# mach_sac.net
KiCad netlist of a schematic drawn in Altium Designer
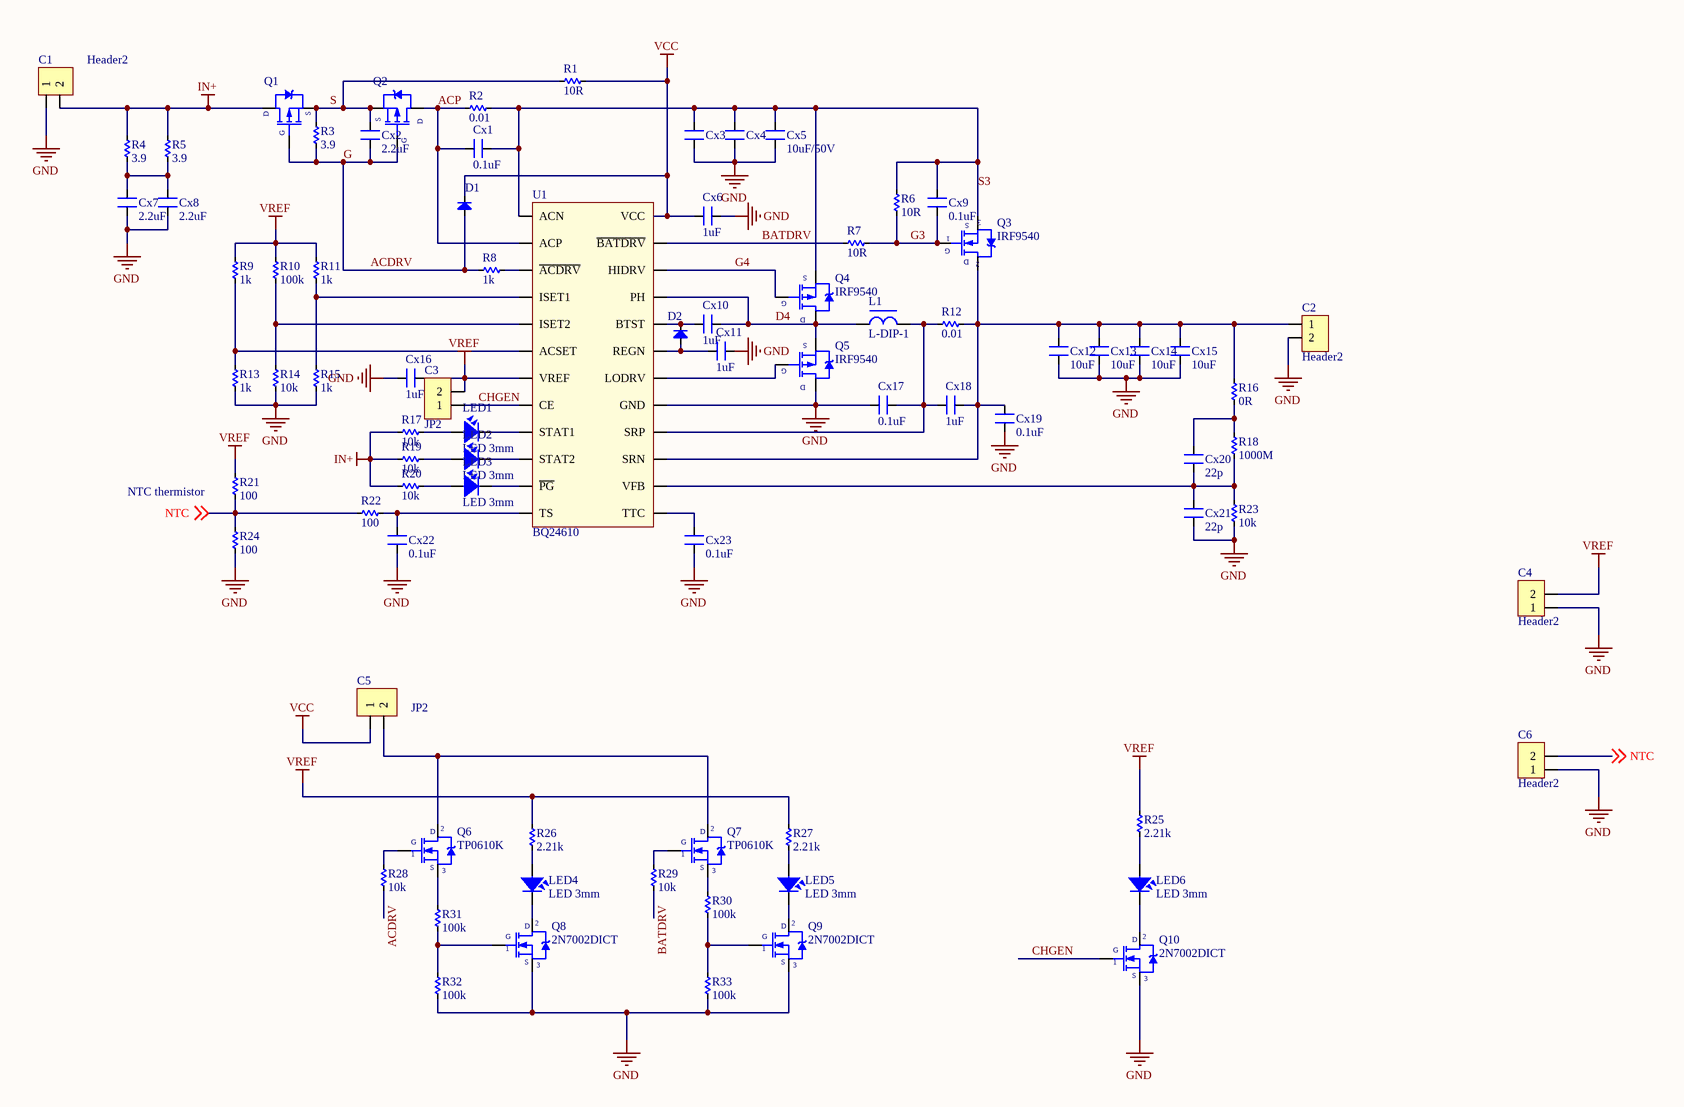
[diagram p0: mach sac.SchDoc]

(export (version "E")
  (design (tool "Eeschema 10.0.6"))
  (components
    (comp (ref "C1")
      (value "Header2")
      (footprint "HDR2")
      (description "Header IDC, 2 x 1 Pin Vertical 2.54mm Pitch (Non-Boxed, Male)")
      (fields
        (field (name "MANUFACTURER") "Würth Elektronik eiSos GmbH")
        (field (name "PARTNO") "613002143121")
        (field (name "CREATED BY") "Karrer Zheng")
      )
      (libsource (lib "") (part "Header2_1"))
    )
    (comp (ref "C2")
      (value "Header2")
      (footprint "HDR2")
      (description "Header IDC, 2 x 1 Pin Vertical 2.54mm Pitch (Non-Boxed, Male)")
      (fields
        (field (name "MANUFACTURER") "Würth Elektronik eiSos GmbH")
        (field (name "PARTNO") "613002143121")
        (field (name "CREATED BY") "Karrer Zheng")
      )
      (libsource (lib "") (part "Header2_2"))
    )
    (comp (ref "C3")
      (value "JP2")
      (footprint "JP2-CLOSED")
      (description "WR-PHD 2.54 mm Angled Socket Header")
      (fields
        (field (name "MANUFACTURER") "Würth Elektronik eiSos GmbH")
        (field (name "PARTNO") "613002143121")
        (field (name "CREATED BY") "Karrer Zheng")
      )
      (libsource (lib "") (part "JP2_1"))
    )
    (comp (ref "C4")
      (value "Header2")
      (footprint "HDR2")
      (description "Header IDC, 2 x 1 Pin Vertical 2.54mm Pitch (Non-Boxed, Male)")
      (fields
        (field (name "MANUFACTURER") "Würth Elektronik eiSos GmbH")
        (field (name "PARTNO") "613002143121")
        (field (name "CREATED BY") "Karrer Zheng")
      )
      (libsource (lib "LIBRARY") (part "Header2"))
    )
    (comp (ref "C5")
      (value "JP2")
      (footprint "JP2-C1T")
      (description "WR-PHD 2.54 mm Angled Socket Header")
      (fields
        (field (name "MANUFACTURER") "Würth Elektronik eiSos GmbH")
        (field (name "PARTNO") "613002143121")
        (field (name "CREATED BY") "Karrer Zheng")
      )
      (libsource (lib "ImetAltiumLibrary") (part "JP2"))
    )
    (comp (ref "C6")
      (value "Header2")
      (footprint "HDR2")
      (description "Header IDC, 2 x 1 Pin Vertical 2.54mm Pitch (Non-Boxed, Male)")
      (fields
        (field (name "MANUFACTURER") "Würth Elektronik eiSos GmbH")
        (field (name "PARTNO") "613002143121")
        (field (name "CREATED BY") "Karrer Zheng")
      )
      (libsource (lib "LIBRARY") (part "Header2"))
    )
    (comp (ref "Cx1") (value "0.1uF") (footprint "C0805") (libsource (lib "LIBRARY") (part "CN")))
    (comp (ref "Cx2") (value "2.2uF") (footprint "C0805") (libsource (lib "LIBRARY") (part "CN")))
    (comp (ref "Cx3") (value "10uF/50V") (footprint "C0805") (libsource (lib "LIBRARY") (part "CN")))
    (comp (ref "Cx4") (value "10uF/50V") (footprint "C0805") (libsource (lib "LIBRARY") (part "CN")))
    (comp (ref "Cx5") (value "10uF/50V") (footprint "C0805") (libsource (lib "LIBRARY") (part "CN")))
    (comp (ref "Cx6") (value "1uF") (footprint "C0805") (libsource (lib "LIBRARY") (part "CN")))
    (comp (ref "Cx7") (value "2.2uF") (footprint "C0805") (libsource (lib "LIBRARY") (part "CN")))
    (comp (ref "Cx8") (value "2.2uF") (footprint "C0805") (libsource (lib "LIBRARY") (part "CN")))
    (comp (ref "Cx9") (value "0.1uF") (footprint "C0805") (libsource (lib "LIBRARY") (part "CN")))
    (comp (ref "Cx10") (value "1uF") (footprint "C0805") (libsource (lib "LIBRARY") (part "CN")))
    (comp (ref "Cx11") (value "1uF") (footprint "C0805") (libsource (lib "LIBRARY") (part "CN")))
    (comp (ref "Cx12") (value "10uF") (footprint "C0805") (libsource (lib "LIBRARY") (part "CN")))
    (comp (ref "Cx13") (value "10uF") (footprint "C0805") (libsource (lib "LIBRARY") (part "CN")))
    (comp (ref "Cx14") (value "10uF") (footprint "C0805") (libsource (lib "LIBRARY") (part "CN")))
    (comp (ref "Cx15") (value "10uF") (footprint "C0805") (libsource (lib "LIBRARY") (part "CN")))
    (comp (ref "Cx16") (value "1uF") (footprint "C0805") (libsource (lib "LIBRARY") (part "CN")))
    (comp (ref "Cx17") (value "0.1uF") (footprint "C0805") (libsource (lib "LIBRARY") (part "CN")))
    (comp (ref "Cx18") (value "1uF") (footprint "C0805") (libsource (lib "LIBRARY") (part "CN")))
    (comp (ref "Cx19") (value "0.1uF") (footprint "C0805") (libsource (lib "LIBRARY") (part "CN")))
    (comp (ref "Cx20") (value "22p") (footprint "C0805") (libsource (lib "LIBRARY") (part "CN")))
    (comp (ref "Cx21") (value "22p") (footprint "C0805") (libsource (lib "LIBRARY") (part "CN")))
    (comp (ref "Cx22") (value "0.1uF") (footprint "C0805") (libsource (lib "LIBRARY") (part "CN")))
    (comp (ref "Cx23") (value "0.1uF") (footprint "C0805") (libsource (lib "LIBRARY") (part "CN")))
    (comp (ref "D1")
      (value "Diode")
      (footprint "DIO-1A")
      (description "Default Diode")
      (fields (field (name "PUBLISHER") "Altium Limited"))
      (libsource (lib "ImetAltiumLibrary") (part "Diode"))
    )
    (comp (ref "D2")
      (value "Diode")
      (footprint "DIO-1A")
      (description "Default Diode")
      (fields (field (name "PUBLISHER") "Altium Limited"))
      (libsource (lib "ImetAltiumLibrary") (part "Diode"))
    )
    (comp (ref "L1")
      (value "L-DIP-1")
      (footprint "L-SMD-D-12.5x12.5")
      (description "Inductor")
      (libsource (lib "ImetAltiumLibrary") (part "L-DIP-1"))
    )
    (comp (ref "LED1")
      (value "LED 3mm")
      (footprint "Led SMD")
      (description "LED Single colour Green and Red")
      (libsource (lib "PELAB") (part "LED 3mm"))
    )
    (comp (ref "LED2")
      (value "LED 3mm")
      (footprint "Led SMD")
      (description "LED Single colour Green and Red")
      (libsource (lib "PELAB") (part "LED 3mm"))
    )
    (comp (ref "LED3")
      (value "LED 3mm")
      (footprint "Led SMD")
      (description "LED Single colour Green and Red")
      (libsource (lib "PELAB") (part "LED 3mm"))
    )
    (comp (ref "LED4")
      (value "LED 3mm")
      (footprint "Led SMD")
      (description "LED Single colour Green and Red")
      (libsource (lib "PELAB") (part "LED 3mm"))
    )
    (comp (ref "LED5")
      (value "LED 3mm")
      (footprint "Led SMD")
      (description "LED Single colour Green and Red")
      (libsource (lib "PELAB") (part "LED 3mm"))
    )
    (comp (ref "LED6")
      (value "LED 3mm")
      (footprint "Led SMD")
      (description "LED Single colour Green and Red")
      (libsource (lib "PELAB") (part "LED 3mm"))
    )
    (comp (ref "Q1")
      (value "IRF9540")
      (footprint "SO-8")
      (description "HEXFET P-Channel Power MOSFET")
      (fields (field (name "PUBLISHER") "Altium Limited"))
      (libsource (lib "PELAB") (part "IRF9540"))
    )
    (comp (ref "Q2")
      (value "IRF9540")
      (footprint "SO-8")
      (description "HEXFET P-Channel Power MOSFET")
      (fields (field (name "PUBLISHER") "Altium Limited"))
      (libsource (lib "ImetAltiumLibrary") (part "IRF9540"))
    )
    (comp (ref "Q3")
      (value "IRF9540")
      (footprint "SO-8")
      (description "MOSFET N - CHANNEL 500V - 0.75 - 8A - TO-220")
      (libsource (lib "ImetAltiumLibrary") (part "IRF840"))
    )
    (comp (ref "Q4")
      (value "IRF9540")
      (footprint "SO-8")
      (description "HEXFET P-Channel Power MOSFET")
      (libsource (lib "LIBRARY") (part "IRF9540"))
    )
    (comp (ref "Q5")
      (value "IRF9540")
      (footprint "SO-8")
      (description "HEXFET P-Channel Power MOSFET")
      (libsource (lib "LIBRARY") (part "IRF9540"))
    )
    (comp (ref "Q6")
      (value "TP0610K")
      (footprint "SOT23-132")
      (description "MOSFET N - CHANNEL 500V - 0.75 - 8A - TO-220")
      (libsource (lib "ImetAltiumLibrary") (part "IRF840"))
    )
    (comp (ref "Q7")
      (value "TP0610K")
      (footprint "SOT23-132")
      (description "MOSFET N - CHANNEL 500V - 0.75 - 8A - TO-220")
      (libsource (lib "ImetAltiumLibrary") (part "IRF840"))
    )
    (comp (ref "Q8")
      (value "2N7002DICT")
      (footprint "SOT23-132")
      (description "MOSFET N - CHANNEL 500V - 0.75 - 8A - TO-220")
      (libsource (lib "ImetAltiumLibrary") (part "IRF840"))
    )
    (comp (ref "Q9")
      (value "2N7002DICT")
      (footprint "SOT23-132")
      (description "MOSFET N - CHANNEL 500V - 0.75 - 8A - TO-220")
      (libsource (lib "ImetAltiumLibrary") (part "IRF840"))
    )
    (comp (ref "Q10")
      (value "2N7002DICT")
      (footprint "SOT23-132")
      (description "MOSFET N - CHANNEL 500V - 0.75 - 8A - TO-220")
      (libsource (lib "ImetAltiumLibrary") (part "IRF840"))
    )
    (comp (ref "R1")
      (value "10R")
      (footprint "Resistor:RES-SMD-0805")
      (description "Resistor")
      (fields
        (field (name "MANUFACTURER") "Generic Components")
        (field (name "PUBLISHER") "Altium Hobart Technology Centre")
      )
      (libsource (lib "LIBRARY") (part "Res-SMD"))
    )
    (comp (ref "R2")
      (value "0.01")
      (footprint "RES-SMD-1210")
      (description "Resistor")
      (fields
        (field (name "MANUFACTURER") "Generic Components")
        (field (name "PUBLISHER") "Altium Hobart Technology Centre")
      )
      (libsource (lib "LIBRARY") (part "Res-SMD"))
    )
    (comp (ref "R3")
      (value "3.9")
      (footprint "Resistor:RES-SMD-0805")
      (description "Resistor")
      (fields
        (field (name "MANUFACTURER") "Generic Components")
        (field (name "PUBLISHER") "Altium Hobart Technology Centre")
      )
      (libsource (lib "LIBRARY") (part "Res-SMD"))
    )
    (comp (ref "R4")
      (value "3.9")
      (footprint "Resistor:RES-SMD-0805")
      (description "Resistor")
      (fields
        (field (name "MANUFACTURER") "Generic Components")
        (field (name "PUBLISHER") "Altium Hobart Technology Centre")
      )
      (libsource (lib "LIBRARY") (part "Res-SMD"))
    )
    (comp (ref "R5")
      (value "3.9")
      (footprint "Resistor:RES-SMD-0805")
      (description "Resistor")
      (fields
        (field (name "MANUFACTURER") "Generic Components")
        (field (name "PUBLISHER") "Altium Hobart Technology Centre")
      )
      (libsource (lib "LIBRARY") (part "Res-SMD"))
    )
    (comp (ref "R6")
      (value "10R")
      (footprint "Resistor:RES-SMD-0805")
      (description "Resistor")
      (fields
        (field (name "MANUFACTURER") "Generic Components")
        (field (name "PUBLISHER") "Altium Hobart Technology Centre")
      )
      (libsource (lib "LIBRARY") (part "Res-SMD"))
    )
    (comp (ref "R7")
      (value "10R")
      (footprint "Resistor:RES-SMD-0805")
      (description "Resistor")
      (fields
        (field (name "MANUFACTURER") "Generic Components")
        (field (name "PUBLISHER") "Altium Hobart Technology Centre")
      )
      (libsource (lib "LIBRARY") (part "Res-SMD"))
    )
    (comp (ref "R8")
      (value "1k")
      (footprint "Resistor:RES-SMD-0805")
      (description "Resistor")
      (fields
        (field (name "MANUFACTURER") "Generic Components")
        (field (name "PUBLISHER") "Altium Hobart Technology Centre")
      )
      (libsource (lib "LIBRARY") (part "Res-SMD"))
    )
    (comp (ref "R9")
      (value "1k")
      (footprint "Resistor:RES-SMD-0805")
      (description "Resistor")
      (fields
        (field (name "MANUFACTURER") "Generic Components")
        (field (name "PUBLISHER") "Altium Hobart Technology Centre")
      )
      (libsource (lib "LIBRARY") (part "Res-SMD"))
    )
    (comp (ref "R10")
      (value "100k")
      (footprint "Resistor:RES-SMD-0805")
      (description "Resistor")
      (fields
        (field (name "MANUFACTURER") "Generic Components")
        (field (name "PUBLISHER") "Altium Hobart Technology Centre")
      )
      (libsource (lib "LIBRARY") (part "Res-SMD"))
    )
    (comp (ref "R11")
      (value "1k")
      (footprint "Resistor:RES-SMD-0805")
      (description "Resistor")
      (fields
        (field (name "MANUFACTURER") "Generic Components")
        (field (name "PUBLISHER") "Altium Hobart Technology Centre")
      )
      (libsource (lib "LIBRARY") (part "Res-SMD"))
    )
    (comp (ref "R12")
      (value "0.01")
      (footprint "RES-SMD-1210")
      (description "Resistor")
      (fields
        (field (name "MANUFACTURER") "Generic Components")
        (field (name "PUBLISHER") "Altium Hobart Technology Centre")
      )
      (libsource (lib "ImetAltiumLibrary") (part "Res-SMD"))
    )
    (comp (ref "R13")
      (value "1k")
      (footprint "Resistor:RES-SMD-0805")
      (description "Resistor")
      (fields
        (field (name "MANUFACTURER") "Generic Components")
        (field (name "PUBLISHER") "Altium Hobart Technology Centre")
      )
      (libsource (lib "LIBRARY") (part "Res-SMD"))
    )
    (comp (ref "R14")
      (value "10k")
      (footprint "Resistor:RES-SMD-0805")
      (description "Resistor")
      (fields
        (field (name "MANUFACTURER") "Generic Components")
        (field (name "PUBLISHER") "Altium Hobart Technology Centre")
      )
      (libsource (lib "LIBRARY") (part "Res-SMD"))
    )
    (comp (ref "R15")
      (value "1k")
      (footprint "Resistor:RES-SMD-0805")
      (description "Resistor")
      (fields
        (field (name "MANUFACTURER") "Generic Components")
        (field (name "PUBLISHER") "Altium Hobart Technology Centre")
      )
      (libsource (lib "LIBRARY") (part "Res-SMD"))
    )
    (comp (ref "R16")
      (value "0R")
      (footprint "Resistor:RES-SMD-0805")
      (description "Resistor")
      (fields
        (field (name "MANUFACTURER") "Generic Components")
        (field (name "PUBLISHER") "Altium Hobart Technology Centre")
      )
      (libsource (lib "LIBRARY") (part "Res-SMD"))
    )
    (comp (ref "R17")
      (value "10k")
      (footprint "Resistor:RES-SMD-0805")
      (description "Resistor")
      (fields
        (field (name "MANUFACTURER") "Generic Components")
        (field (name "PUBLISHER") "Altium Hobart Technology Centre")
      )
      (libsource (lib "LIBRARY") (part "Res-SMD"))
    )
    (comp (ref "R18")
      (value "1000M")
      (footprint "Resistor:RES-SMD-0805")
      (description "Resistor")
      (fields
        (field (name "MANUFACTURER") "Generic Components")
        (field (name "PUBLISHER") "Altium Hobart Technology Centre")
      )
      (libsource (lib "LIBRARY") (part "Res-SMD"))
    )
    (comp (ref "R19")
      (value "10k")
      (footprint "Resistor:RES-SMD-0805")
      (description "Resistor")
      (fields
        (field (name "MANUFACTURER") "Generic Components")
        (field (name "PUBLISHER") "Altium Hobart Technology Centre")
      )
      (libsource (lib "LIBRARY") (part "Res-SMD"))
    )
    (comp (ref "R20")
      (value "10k")
      (footprint "Resistor:RES-SMD-0805")
      (description "Resistor")
      (fields
        (field (name "MANUFACTURER") "Generic Components")
        (field (name "PUBLISHER") "Altium Hobart Technology Centre")
      )
      (libsource (lib "LIBRARY") (part "Res-SMD"))
    )
    (comp (ref "R21")
      (value "100")
      (footprint "Resistor:RES-SMD-0805")
      (description "Resistor")
      (fields
        (field (name "MANUFACTURER") "Generic Components")
        (field (name "PUBLISHER") "Altium Hobart Technology Centre")
      )
      (libsource (lib "LIBRARY") (part "Res-SMD"))
    )
    (comp (ref "R22")
      (value "100")
      (footprint "Resistor:RES-SMD-0805")
      (description "Resistor")
      (fields
        (field (name "MANUFACTURER") "Generic Components")
        (field (name "PUBLISHER") "Altium Hobart Technology Centre")
      )
      (libsource (lib "LIBRARY") (part "Res-SMD"))
    )
    (comp (ref "R23")
      (value "10k")
      (footprint "Resistor:RES-SMD-0805")
      (description "Resistor")
      (fields
        (field (name "MANUFACTURER") "Generic Components")
        (field (name "PUBLISHER") "Altium Hobart Technology Centre")
      )
      (libsource (lib "ImetAltiumLibrary") (part "Res-SMD"))
    )
    (comp (ref "R24")
      (value "100")
      (footprint "Resistor:RES-SMD-0805")
      (description "Resistor")
      (fields
        (field (name "MANUFACTURER") "Generic Components")
        (field (name "PUBLISHER") "Altium Hobart Technology Centre")
      )
      (libsource (lib "LIBRARY") (part "Res-SMD"))
    )
    (comp (ref "R25")
      (value "2.21k")
      (footprint "RES-SMD-0603")
      (description "Resistor")
      (fields
        (field (name "MANUFACTURER") "Generic Components")
        (field (name "PUBLISHER") "Altium Hobart Technology Centre")
      )
      (libsource (lib "ImetAltiumLibrary") (part "Res-SMD"))
    )
    (comp (ref "R26")
      (value "2.21k")
      (footprint "RES-SMD-0603")
      (description "Resistor")
      (fields
        (field (name "MANUFACTURER") "Generic Components")
        (field (name "PUBLISHER") "Altium Hobart Technology Centre")
      )
      (libsource (lib "ImetAltiumLibrary") (part "Res-SMD"))
    )
    (comp (ref "R27")
      (value "2.21k")
      (footprint "RES-SMD-0603")
      (description "Resistor")
      (fields
        (field (name "MANUFACTURER") "Generic Components")
        (field (name "PUBLISHER") "Altium Hobart Technology Centre")
      )
      (libsource (lib "ImetAltiumLibrary") (part "Res-SMD"))
    )
    (comp (ref "R28")
      (value "10k")
      (footprint "RES-SMD-0603")
      (description "Resistor")
      (fields
        (field (name "MANUFACTURER") "Generic Components")
        (field (name "PUBLISHER") "Altium Hobart Technology Centre")
      )
      (libsource (lib "ImetAltiumLibrary") (part "Res-SMD"))
    )
    (comp (ref "R29")
      (value "10k")
      (footprint "RES-SMD-0603")
      (description "Resistor")
      (fields
        (field (name "MANUFACTURER") "Generic Components")
        (field (name "PUBLISHER") "Altium Hobart Technology Centre")
      )
      (libsource (lib "ImetAltiumLibrary") (part "Res-SMD"))
    )
    (comp (ref "R30")
      (value "100k")
      (footprint "RES-SMD-0603")
      (description "Resistor")
      (fields
        (field (name "MANUFACTURER") "Generic Components")
        (field (name "PUBLISHER") "Altium Hobart Technology Centre")
      )
      (libsource (lib "ImetAltiumLibrary") (part "Res-SMD"))
    )
    (comp (ref "R31")
      (value "100k")
      (footprint "RES-SMD-0603")
      (description "Resistor")
      (fields
        (field (name "MANUFACTURER") "Generic Components")
        (field (name "PUBLISHER") "Altium Hobart Technology Centre")
      )
      (libsource (lib "ImetAltiumLibrary") (part "Res-SMD"))
    )
    (comp (ref "R32")
      (value "100k")
      (footprint "RES-SMD-0603")
      (description "Resistor")
      (fields
        (field (name "MANUFACTURER") "Generic Components")
        (field (name "PUBLISHER") "Altium Hobart Technology Centre")
      )
      (libsource (lib "ImetAltiumLibrary") (part "Res-SMD"))
    )
    (comp (ref "R33")
      (value "100k")
      (footprint "RES-SMD-0603")
      (description "Resistor")
      (fields
        (field (name "MANUFACTURER") "Generic Components")
        (field (name "PUBLISHER") "Altium Hobart Technology Centre")
      )
      (libsource (lib "ImetAltiumLibrary") (part "Res-SMD"))
    )
    (comp (ref "U1")
      (value "BQ24610")
      (footprint "QFN50P400X400X100_HS-25N")
      (description "DIP24")
      (libsource (lib "PELAB") (part "BQ24610"))
    )
  )
  (nets
    (net (code "1") (name "/ACDRV") (class "Default")
      (node (ref "Cx2") (pin "1") (pinfunction "1_1") (pintype "passive"))
      (node (ref "D1") (pin "1") (pinfunction "A_1") (pintype "passive"))
      (node (ref "Q1") (pin "1") (pinfunction "G_1") (pintype "passive"))
      (node (ref "Q2") (pin "1") (pinfunction "G_1") (pintype "passive"))
      (node (ref "R28") (pin "2") (pinfunction "2_2") (pintype "passive"))
      (node (ref "R3") (pin "2") (pinfunction "2_2") (pintype "passive"))
      (node (ref "R8") (pin "1") (pinfunction "1_1") (pintype "passive"))
    )
    (net (code "2") (name "/ACP") (class "Default")
      (node (ref "Cx1") (pin "2") (pinfunction "2_2") (pintype "passive"))
      (node (ref "Q2") (pin "2") (pinfunction "D_2") (pintype "passive"))
      (node (ref "R2") (pin "2") (pinfunction "2_2") (pintype "passive"))
      (node (ref "U1") (pin "2") (pinfunction "ACP_2") (pintype "passive"))
    )
    (net (code "3") (name "/BATDRV") (class "Default")
      (node (ref "R29") (pin "2") (pinfunction "2_2") (pintype "passive"))
      (node (ref "R7") (pin "1") (pinfunction "1_1") (pintype "passive"))
      (node (ref "U1") (pin "23") (pinfunction "~{BATDRV}_23") (pintype "passive"))
    )
    (net (code "4") (name "/CHGEN") (class "Default")
      (node (ref "C3") (pin "1") (pinfunction "1_1") (pintype "passive"))
      (node (ref "Q10") (pin "1") (pinfunction "G_1") (pintype "passive"))
      (node (ref "U1") (pin "4") (pinfunction "CE_4") (pintype "passive"))
    )
    (net (code "5") (name "/D4") (class "Default")
      (node (ref "Cx10") (pin "1") (pinfunction "1_1") (pintype "passive"))
      (node (ref "L1") (pin "1") (pinfunction "1_1") (pintype "passive"))
      (node (ref "Q4") (pin "2") (pinfunction "D_2") (pintype "passive"))
      (node (ref "Q5") (pin "3") (pinfunction "S_3") (pintype "passive"))
      (node (ref "U1") (pin "20") (pinfunction "PH_20") (pintype "passive"))
    )
    (net (code "6") (name "/G3") (class "Default")
      (node (ref "Cx9") (pin "2") (pinfunction "2_2") (pintype "passive"))
      (node (ref "Q3") (pin "1") (pinfunction "G_1") (pintype "passive"))
      (node (ref "R6") (pin "1") (pinfunction "1_1") (pintype "passive"))
      (node (ref "R7") (pin "2") (pinfunction "2_2") (pintype "passive"))
    )
    (net (code "7") (name "/G4") (class "Default")
      (node (ref "Q4") (pin "1") (pinfunction "G_1") (pintype "passive"))
      (node (ref "U1") (pin "21") (pinfunction "HIDRV_21") (pintype "passive"))
    )
    (net (code "8") (name "/S") (class "Default")
      (node (ref "Cx2") (pin "2") (pinfunction "2_2") (pintype "passive"))
      (node (ref "Q1") (pin "3") (pinfunction "S_3") (pintype "passive"))
      (node (ref "Q2") (pin "3") (pinfunction "S_3") (pintype "passive"))
      (node (ref "R1") (pin "1") (pinfunction "1_1") (pintype "passive"))
      (node (ref "R3") (pin "1") (pinfunction "1_1") (pintype "passive"))
    )
    (net (code "9") (name "/S3") (class "Default")
      (node (ref "Cx1") (pin "1") (pinfunction "1_1") (pintype "passive"))
      (node (ref "Cx3") (pin "1") (pinfunction "1_1") (pintype "passive"))
      (node (ref "Cx4") (pin "1") (pinfunction "1_1") (pintype "passive"))
      (node (ref "Cx5") (pin "1") (pinfunction "1_1") (pintype "passive"))
      (node (ref "Cx9") (pin "1") (pinfunction "1_1") (pintype "passive"))
      (node (ref "Q3") (pin "3") (pinfunction "S_3") (pintype "passive"))
      (node (ref "Q4") (pin "3") (pinfunction "S_3") (pintype "passive"))
      (node (ref "R2") (pin "1") (pinfunction "1_1") (pintype "passive"))
      (node (ref "R6") (pin "2") (pinfunction "2_2") (pintype "passive"))
      (node (ref "U1") (pin "1") (pinfunction "ACN_1") (pintype "passive"))
    )
    (net (code "10") (name "GND") (class "Default")
      (node (ref "C1") (pin "1") (pinfunction "1_1") (pintype "passive"))
      (node (ref "C2") (pin "2") (pinfunction "2_2") (pintype "passive"))
      (node (ref "C4") (pin "1") (pinfunction "1_1") (pintype "passive"))
      (node (ref "C6") (pin "1") (pinfunction "1_1") (pintype "passive"))
      (node (ref "Cx11") (pin "1") (pinfunction "1_1") (pintype "passive"))
      (node (ref "Cx12") (pin "2") (pinfunction "2_2") (pintype "passive"))
      (node (ref "Cx13") (pin "2") (pinfunction "2_2") (pintype "passive"))
      (node (ref "Cx14") (pin "2") (pinfunction "2_2") (pintype "passive"))
      (node (ref "Cx15") (pin "2") (pinfunction "2_2") (pintype "passive"))
      (node (ref "Cx16") (pin "1") (pinfunction "1_1") (pintype "passive"))
      (node (ref "Cx17") (pin "2") (pinfunction "2_2") (pintype "passive"))
      (node (ref "Cx19") (pin "2") (pinfunction "2_2") (pintype "passive"))
      (node (ref "Cx21") (pin "2") (pinfunction "2_2") (pintype "passive"))
      (node (ref "Cx22") (pin "2") (pinfunction "2_2") (pintype "passive"))
      (node (ref "Cx23") (pin "2") (pinfunction "2_2") (pintype "passive"))
      (node (ref "Cx3") (pin "2") (pinfunction "2_2") (pintype "passive"))
      (node (ref "Cx4") (pin "2") (pinfunction "2_2") (pintype "passive"))
      (node (ref "Cx5") (pin "2") (pinfunction "2_2") (pintype "passive"))
      (node (ref "Cx6") (pin "1") (pinfunction "1_1") (pintype "passive"))
      (node (ref "Cx7") (pin "1") (pinfunction "1_1") (pintype "passive"))
      (node (ref "Cx8") (pin "1") (pinfunction "1_1") (pintype "passive"))
      (node (ref "Q10") (pin "3") (pinfunction "S_3") (pintype "passive"))
      (node (ref "Q5") (pin "2") (pinfunction "D_2") (pintype "passive"))
      (node (ref "Q8") (pin "3") (pinfunction "S_3") (pintype "passive"))
      (node (ref "Q9") (pin "3") (pinfunction "S_3") (pintype "passive"))
      (node (ref "R13") (pin "1") (pinfunction "1_1") (pintype "passive"))
      (node (ref "R14") (pin "1") (pinfunction "1_1") (pintype "passive"))
      (node (ref "R15") (pin "1") (pinfunction "1_1") (pintype "passive"))
      (node (ref "R23") (pin "2") (pinfunction "2_2") (pintype "passive"))
      (node (ref "R24") (pin "1") (pinfunction "1_1") (pintype "passive"))
      (node (ref "R32") (pin "2") (pinfunction "2_2") (pintype "passive"))
      (node (ref "R33") (pin "2") (pinfunction "2_2") (pintype "passive"))
      (node (ref "U1") (pin "17") (pinfunction "GND_17") (pintype "passive"))
    )
    (net (code "11") (name "IN+") (class "Default")
      (node (ref "C1") (pin "2") (pinfunction "2_2") (pintype "passive"))
      (node (ref "Q1") (pin "2") (pinfunction "D_2") (pintype "passive"))
      (node (ref "R17") (pin "2") (pinfunction "2_2") (pintype "passive"))
      (node (ref "R19") (pin "2") (pinfunction "2_2") (pintype "passive"))
      (node (ref "R20") (pin "2") (pinfunction "2_2") (pintype "passive"))
      (node (ref "R4") (pin "1") (pinfunction "1_1") (pintype "passive"))
      (node (ref "R5") (pin "1") (pinfunction "1_1") (pintype "passive"))
    )
    (net (code "12") (name "NTC") (class "Default")
      (node (ref "C6") (pin "2") (pinfunction "2_2") (pintype "passive"))
      (node (ref "R21") (pin "1") (pinfunction "1_1") (pintype "passive"))
      (node (ref "R22") (pin "1") (pinfunction "1_1") (pintype "passive"))
      (node (ref "R24") (pin "2") (pinfunction "2_2") (pintype "passive"))
    )
    (net (code "13") (name "Net-(Cx7-Pad2)") (class "Default")
      (node (ref "Cx7") (pin "2") (pinfunction "2_2") (pintype "passive"))
      (node (ref "Cx8") (pin "2") (pinfunction "2_2") (pintype "passive"))
      (node (ref "R4") (pin "2") (pinfunction "2_2") (pintype "passive"))
      (node (ref "R5") (pin "2") (pinfunction "2_2") (pintype "passive"))
    )
    (net (code "14") (name "Net-(Cx20-Pad1)") (class "Default")
      (node (ref "Cx20") (pin "1") (pinfunction "1_1") (pintype "passive"))
      (node (ref "R16") (pin "2") (pinfunction "2_2") (pintype "passive"))
      (node (ref "R18") (pin "1") (pinfunction "1_1") (pintype "passive"))
    )
    (net (code "15") (name "Net-(D2-A)") (class "Default")
      (node (ref "Cx11") (pin "2") (pinfunction "2_2") (pintype "passive"))
      (node (ref "D2") (pin "1") (pinfunction "A_1") (pintype "passive"))
      (node (ref "U1") (pin "18") (pinfunction "REGN_18") (pintype "passive"))
    )
    (net (code "16") (name "Net-(D2-K)") (class "Default")
      (node (ref "Cx10") (pin "2") (pinfunction "2_2") (pintype "passive"))
      (node (ref "D2") (pin "2") (pinfunction "K_2") (pintype "passive"))
      (node (ref "U1") (pin "22") (pinfunction "BTST_22") (pintype "passive"))
    )
    (net (code "17") (name "Net-(LED1-Pad1)") (class "Default")
      (node (ref "LED1") (pin "1") (pinfunction "1_1") (pintype "passive"))
      (node (ref "R17") (pin "1") (pinfunction "1_1") (pintype "passive"))
    )
    (net (code "18") (name "Net-(LED2-Pad1)") (class "Default")
      (node (ref "LED2") (pin "1") (pinfunction "1_1") (pintype "passive"))
      (node (ref "R19") (pin "1") (pinfunction "1_1") (pintype "passive"))
    )
    (net (code "19") (name "Net-(LED3-Pad1)") (class "Default")
      (node (ref "LED3") (pin "1") (pinfunction "1_1") (pintype "passive"))
      (node (ref "R20") (pin "1") (pinfunction "1_1") (pintype "passive"))
    )
    (net (code "20") (name "Net-(LED4-Pad1)") (class "Default")
      (node (ref "LED4") (pin "1") (pinfunction "1_1") (pintype "passive"))
      (node (ref "R26") (pin "2") (pinfunction "2_2") (pintype "passive"))
    )
    (net (code "21") (name "Net-(LED5-Pad1)") (class "Default")
      (node (ref "LED5") (pin "1") (pinfunction "1_1") (pintype "passive"))
      (node (ref "R27") (pin "2") (pinfunction "2_2") (pintype "passive"))
    )
    (net (code "22") (name "Net-(LED6-Pad1)") (class "Default")
      (node (ref "LED6") (pin "1") (pinfunction "1_1") (pintype "passive"))
      (node (ref "R25") (pin "2") (pinfunction "2_2") (pintype "passive"))
    )
    (net (code "23") (name "Net-(Q3-D)") (class "Default")
      (node (ref "C2") (pin "1") (pinfunction "1_1") (pintype "passive"))
      (node (ref "Cx12") (pin "1") (pinfunction "1_1") (pintype "passive"))
      (node (ref "Cx13") (pin "1") (pinfunction "1_1") (pintype "passive"))
      (node (ref "Cx14") (pin "1") (pinfunction "1_1") (pintype "passive"))
      (node (ref "Cx15") (pin "1") (pinfunction "1_1") (pintype "passive"))
      (node (ref "Cx18") (pin "1") (pinfunction "1_1") (pintype "passive"))
      (node (ref "Cx19") (pin "1") (pinfunction "1_1") (pintype "passive"))
      (node (ref "Q3") (pin "2") (pinfunction "D_2") (pintype "passive"))
      (node (ref "R12") (pin "1") (pinfunction "1_1") (pintype "passive"))
      (node (ref "R16") (pin "1") (pinfunction "1_1") (pintype "passive"))
      (node (ref "U1") (pin "13") (pinfunction "SRN_13") (pintype "passive"))
    )
    (net (code "24") (name "Net-(Q5-G)") (class "Default")
      (node (ref "Q5") (pin "1") (pinfunction "G_1") (pintype "passive"))
      (node (ref "U1") (pin "19") (pinfunction "LODRV_19") (pintype "passive"))
    )
    (net (code "25") (name "Net-(Q6-D)") (class "Default")
      (node (ref "C5") (pin "2") (pinfunction "2_2") (pintype "passive"))
      (node (ref "Q6") (pin "2") (pinfunction "D_2") (pintype "passive"))
      (node (ref "Q7") (pin "2") (pinfunction "D_2") (pintype "passive"))
    )
    (net (code "26") (name "Net-(Q6-G)") (class "Default")
      (node (ref "Q6") (pin "1") (pinfunction "G_1") (pintype "passive"))
      (node (ref "R28") (pin "1") (pinfunction "1_1") (pintype "passive"))
    )
    (net (code "27") (name "Net-(Q6-S)") (class "Default")
      (node (ref "Q6") (pin "3") (pinfunction "S_3") (pintype "passive"))
      (node (ref "R31") (pin "1") (pinfunction "1_1") (pintype "passive"))
    )
    (net (code "28") (name "Net-(Q7-G)") (class "Default")
      (node (ref "Q7") (pin "1") (pinfunction "G_1") (pintype "passive"))
      (node (ref "R29") (pin "1") (pinfunction "1_1") (pintype "passive"))
    )
    (net (code "29") (name "Net-(Q7-S)") (class "Default")
      (node (ref "Q7") (pin "3") (pinfunction "S_3") (pintype "passive"))
      (node (ref "R30") (pin "1") (pinfunction "1_1") (pintype "passive"))
    )
    (net (code "30") (name "Net-(Q8-D)") (class "Default")
      (node (ref "LED4") (pin "2") (pinfunction "2_2") (pintype "passive"))
      (node (ref "Q8") (pin "2") (pinfunction "D_2") (pintype "passive"))
    )
    (net (code "31") (name "Net-(Q8-G)") (class "Default")
      (node (ref "Q8") (pin "1") (pinfunction "G_1") (pintype "passive"))
      (node (ref "R31") (pin "2") (pinfunction "2_2") (pintype "passive"))
      (node (ref "R32") (pin "1") (pinfunction "1_1") (pintype "passive"))
    )
    (net (code "32") (name "Net-(Q9-D)") (class "Default")
      (node (ref "LED5") (pin "2") (pinfunction "2_2") (pintype "passive"))
      (node (ref "Q9") (pin "2") (pinfunction "D_2") (pintype "passive"))
    )
    (net (code "33") (name "Net-(Q9-G)") (class "Default")
      (node (ref "Q9") (pin "1") (pinfunction "G_1") (pintype "passive"))
      (node (ref "R30") (pin "2") (pinfunction "2_2") (pintype "passive"))
      (node (ref "R33") (pin "1") (pinfunction "1_1") (pintype "passive"))
    )
    (net (code "34") (name "Net-(Q10-D)") (class "Default")
      (node (ref "LED6") (pin "2") (pinfunction "2_2") (pintype "passive"))
      (node (ref "Q10") (pin "2") (pinfunction "D_2") (pintype "passive"))
    )
    (net (code "35") (name "Net-(U1-ACSET)") (class "Default")
      (node (ref "R13") (pin "2") (pinfunction "2_2") (pintype "passive"))
      (node (ref "R9") (pin "1") (pinfunction "1_1") (pintype "passive"))
      (node (ref "U1") (pin "16") (pinfunction "ACSET_16") (pintype "passive"))
    )
    (net (code "36") (name "Net-(U1-ISET1)") (class "Default")
      (node (ref "R11") (pin "1") (pinfunction "1_1") (pintype "passive"))
      (node (ref "R15") (pin "2") (pinfunction "2_2") (pintype "passive"))
      (node (ref "U1") (pin "11") (pinfunction "ISET1_11") (pintype "passive"))
    )
    (net (code "37") (name "Net-(U1-ISET2)") (class "Default")
      (node (ref "R10") (pin "1") (pinfunction "1_1") (pintype "passive"))
      (node (ref "R14") (pin "2") (pinfunction "2_2") (pintype "passive"))
      (node (ref "U1") (pin "15") (pinfunction "ISET2_15") (pintype "passive"))
    )
    (net (code "38") (name "Net-(U1-SRP)") (class "Default")
      (node (ref "Cx17") (pin "1") (pinfunction "1_1") (pintype "passive"))
      (node (ref "Cx18") (pin "2") (pinfunction "2_2") (pintype "passive"))
      (node (ref "L1") (pin "2") (pinfunction "2_2") (pintype "passive"))
      (node (ref "R12") (pin "2") (pinfunction "2_2") (pintype "passive"))
      (node (ref "U1") (pin "14") (pinfunction "SRP_14") (pintype "passive"))
    )
    (net (code "39") (name "Net-(U1-STAT1)") (class "Default")
      (node (ref "LED1") (pin "2") (pinfunction "2_2") (pintype "passive"))
      (node (ref "U1") (pin "5") (pinfunction "STAT1_5") (pintype "passive"))
    )
    (net (code "40") (name "Net-(U1-STAT2)") (class "Default")
      (node (ref "LED2") (pin "2") (pinfunction "2_2") (pintype "passive"))
      (node (ref "U1") (pin "9") (pinfunction "STAT2_9") (pintype "passive"))
    )
    (net (code "41") (name "Net-(U1-TS)") (class "Default")
      (node (ref "Cx22") (pin "1") (pinfunction "1_1") (pintype "passive"))
      (node (ref "R22") (pin "2") (pinfunction "2_2") (pintype "passive"))
      (node (ref "U1") (pin "6") (pinfunction "TS_6") (pintype "passive"))
    )
    (net (code "42") (name "Net-(U1-TTC)") (class "Default")
      (node (ref "Cx23") (pin "1") (pinfunction "1_1") (pintype "passive"))
      (node (ref "U1") (pin "7") (pinfunction "TTC_7") (pintype "passive"))
    )
    (net (code "43") (name "Net-(U1-VFB)") (class "Default")
      (node (ref "Cx20") (pin "2") (pinfunction "2_2") (pintype "passive"))
      (node (ref "Cx21") (pin "1") (pinfunction "1_1") (pintype "passive"))
      (node (ref "R18") (pin "2") (pinfunction "2_2") (pintype "passive"))
      (node (ref "R23") (pin "1") (pinfunction "1_1") (pintype "passive"))
      (node (ref "U1") (pin "12") (pinfunction "VFB_12") (pintype "passive"))
    )
    (net (code "44") (name "Net-(U1-~{ACDRV})") (class "Default")
      (node (ref "R8") (pin "2") (pinfunction "2_2") (pintype "passive"))
      (node (ref "U1") (pin "3") (pinfunction "~{ACDRV}_3") (pintype "passive"))
    )
    (net (code "45") (name "Net-(U1-~{PG})") (class "Default")
      (node (ref "LED3") (pin "2") (pinfunction "2_2") (pintype "passive"))
      (node (ref "U1") (pin "8") (pinfunction "~{PG}_8") (pintype "passive"))
    )
    (net (code "46") (name "VCC") (class "Default")
      (node (ref "C5") (pin "1") (pinfunction "1_1") (pintype "passive"))
      (node (ref "Cx6") (pin "2") (pinfunction "2_2") (pintype "passive"))
      (node (ref "D1") (pin "2") (pinfunction "K_2") (pintype "passive"))
      (node (ref "R1") (pin "2") (pinfunction "2_2") (pintype "passive"))
      (node (ref "U1") (pin "24") (pinfunction "VCC_24") (pintype "passive"))
    )
    (net (code "47") (name "VREF") (class "Default")
      (node (ref "C3") (pin "2") (pinfunction "2_2") (pintype "passive"))
      (node (ref "C4") (pin "2") (pinfunction "2_2") (pintype "passive"))
      (node (ref "Cx16") (pin "2") (pinfunction "2_2") (pintype "passive"))
      (node (ref "R10") (pin "2") (pinfunction "2_2") (pintype "passive"))
      (node (ref "R11") (pin "2") (pinfunction "2_2") (pintype "passive"))
      (node (ref "R21") (pin "2") (pinfunction "2_2") (pintype "passive"))
      (node (ref "R25") (pin "1") (pinfunction "1_1") (pintype "passive"))
      (node (ref "R26") (pin "1") (pinfunction "1_1") (pintype "passive"))
      (node (ref "R27") (pin "1") (pinfunction "1_1") (pintype "passive"))
      (node (ref "R9") (pin "2") (pinfunction "2_2") (pintype "passive"))
      (node (ref "U1") (pin "10") (pinfunction "VREF_10") (pintype "passive"))
    )
  )
)
